# ProPrj_USB__2026-03-28.net
KiCad netlist of a schematic drawn in EasyEDA Pro
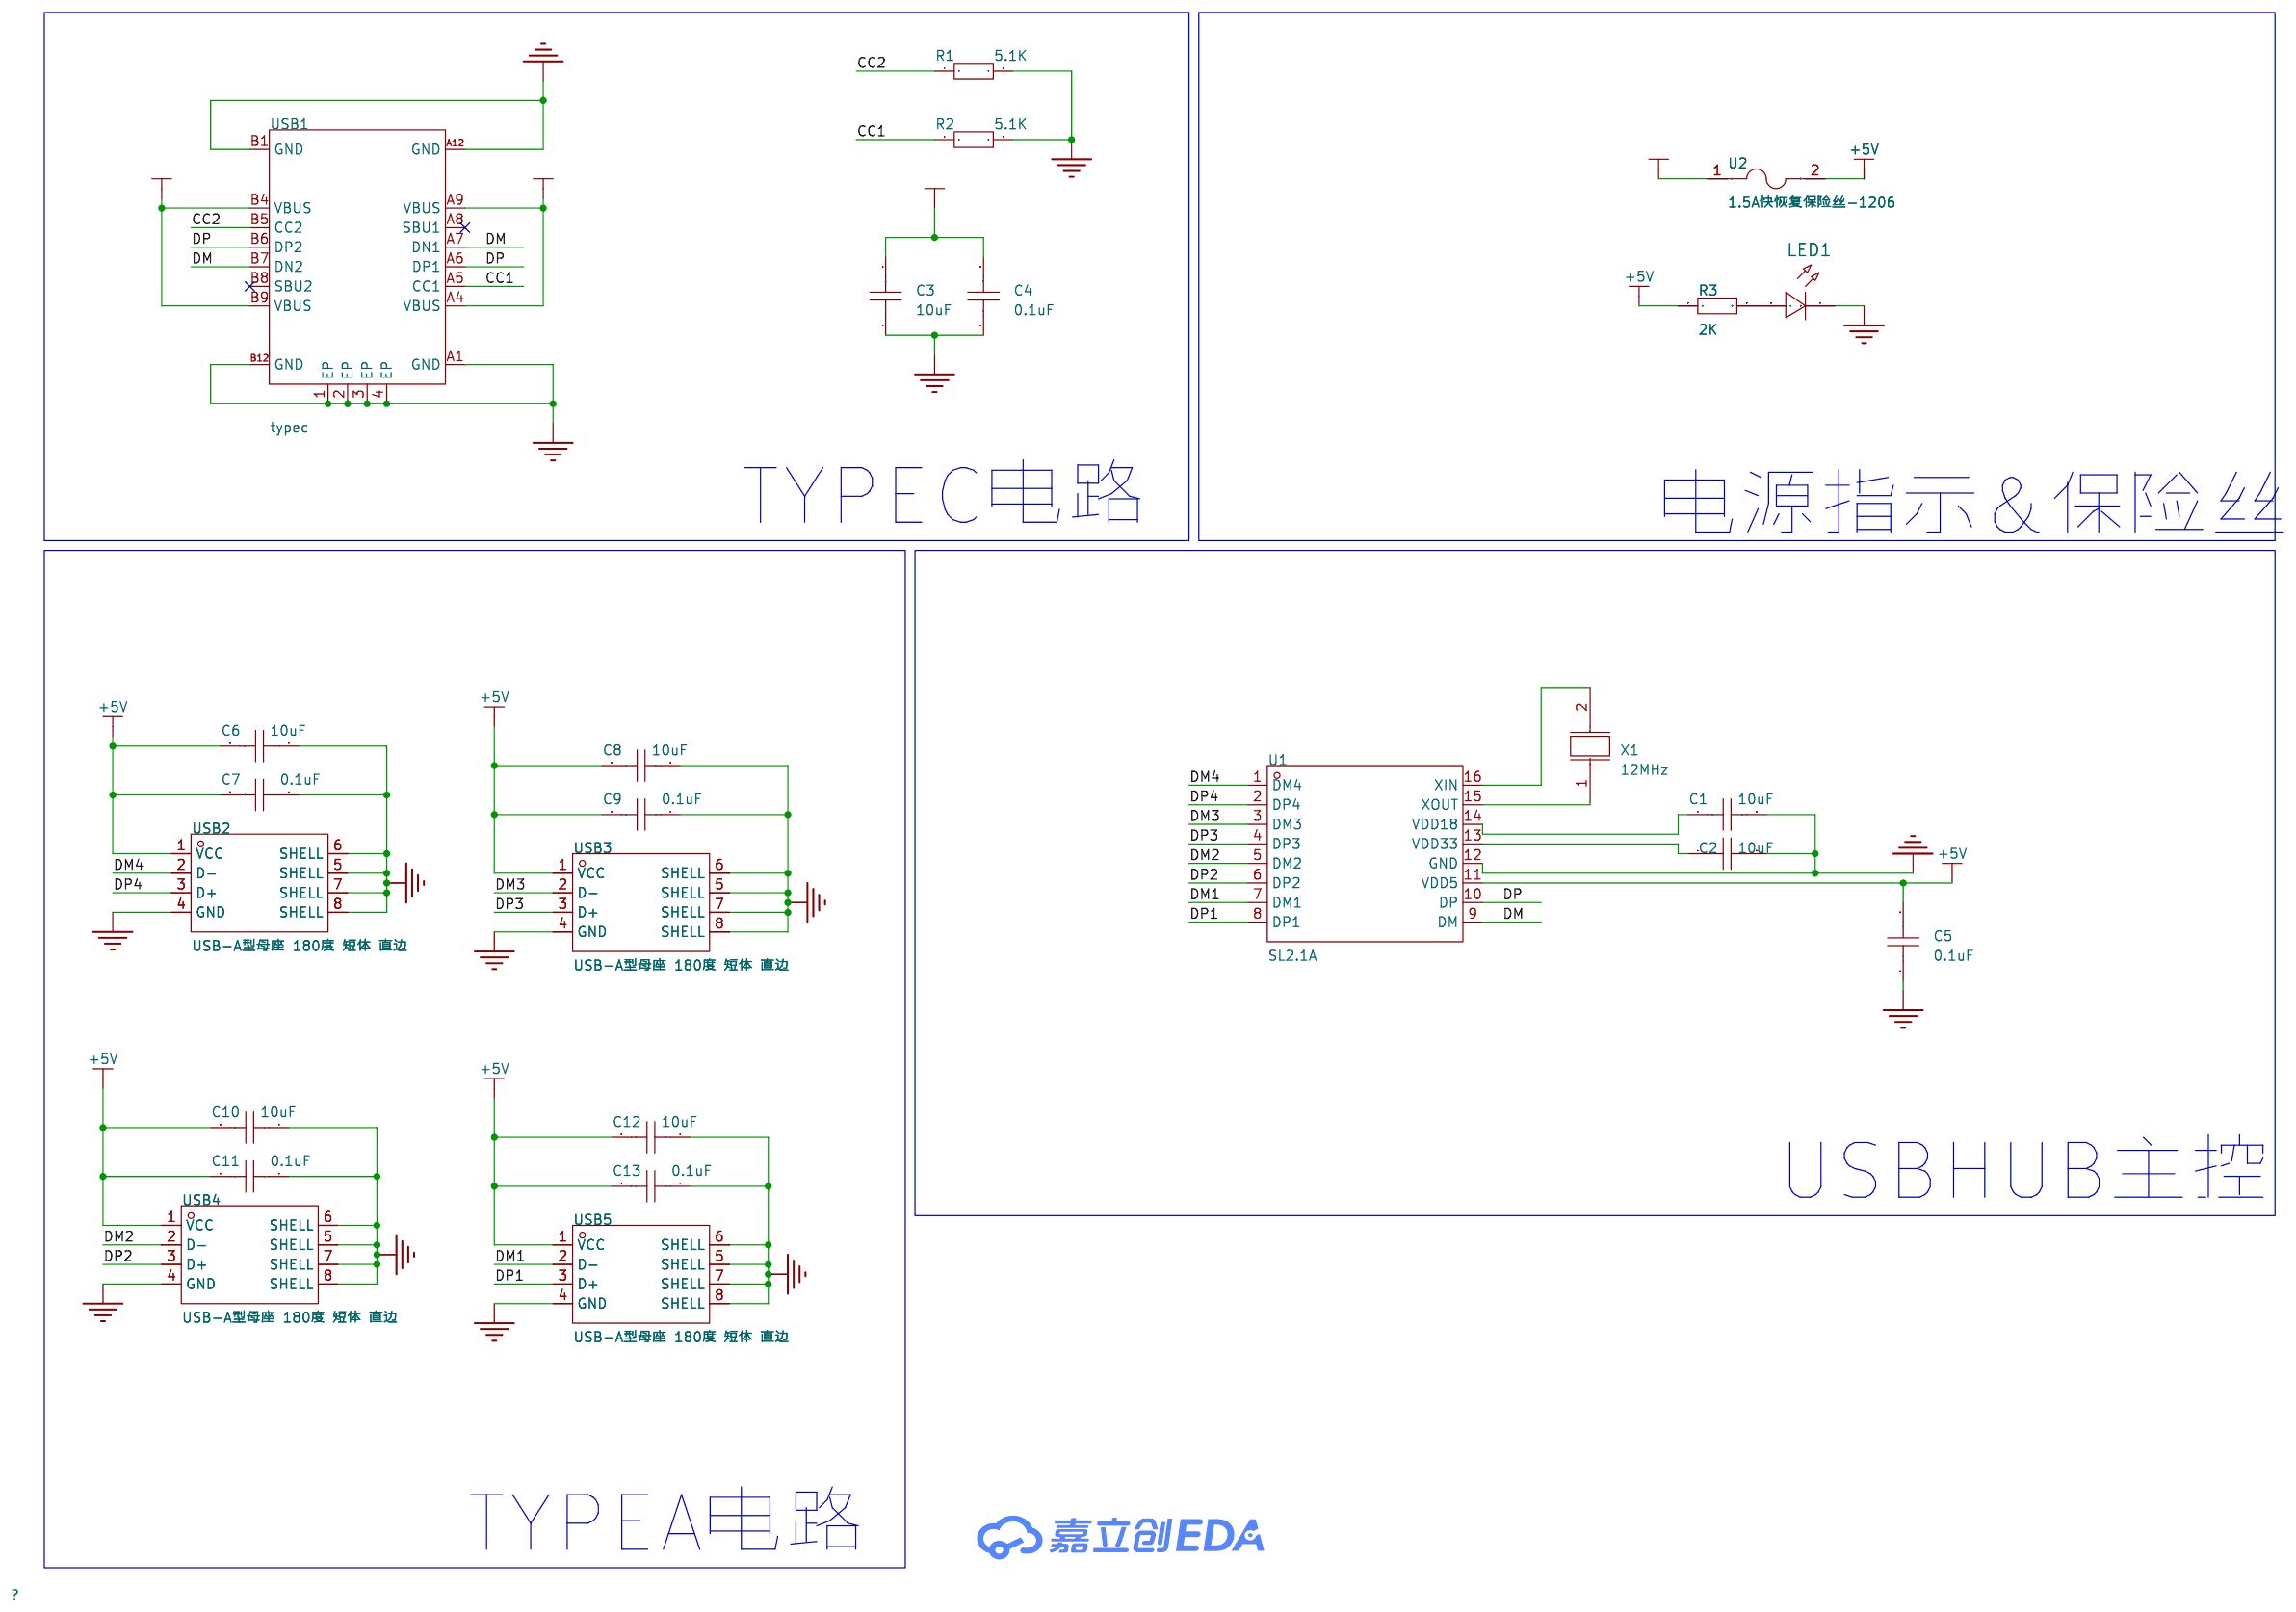
[diagram p0: schematic sheet]

(export (version "E")
  (design (tool "Eeschema 10.0.6"))
  (components
    (comp (ref "C1")
      (value "10uF")
      (footprint "easyedapro:C0805")
      (libsource (lib "easyedapro") (part "Capacitance"))
    )
    (comp (ref "C2")
      (value "10uF")
      (footprint "easyedapro:C0805")
      (libsource (lib "easyedapro") (part "Capacitance"))
    )
    (comp (ref "C3")
      (value "10uF")
      (footprint "easyedapro:C0805")
      (libsource (lib "easyedapro") (part "Capacitance"))
    )
    (comp (ref "C4")
      (value "0.1uF")
      (footprint "easyedapro:C0805")
      (libsource (lib "easyedapro") (part "Capacitance"))
    )
    (comp (ref "C5")
      (value "0.1uF")
      (footprint "easyedapro:C0805")
      (libsource (lib "easyedapro") (part "Capacitance"))
    )
    (comp (ref "C6")
      (value "10uF")
      (footprint "easyedapro:C0805")
      (libsource (lib "easyedapro") (part "Capacitance"))
    )
    (comp (ref "C7")
      (value "0.1uF")
      (footprint "easyedapro:C0805")
      (libsource (lib "easyedapro") (part "Capacitance"))
    )
    (comp (ref "C8")
      (value "10uF")
      (footprint "easyedapro:C0805")
      (libsource (lib "easyedapro") (part "Capacitance"))
    )
    (comp (ref "C9")
      (value "0.1uF")
      (footprint "easyedapro:C0805")
      (libsource (lib "easyedapro") (part "Capacitance"))
    )
    (comp (ref "C10")
      (value "10uF")
      (footprint "easyedapro:C0805")
      (libsource (lib "easyedapro") (part "Capacitance"))
    )
    (comp (ref "C11")
      (value "0.1uF")
      (footprint "easyedapro:C0805")
      (libsource (lib "easyedapro") (part "Capacitance"))
    )
    (comp (ref "C12")
      (value "10uF")
      (footprint "easyedapro:C0805")
      (libsource (lib "easyedapro") (part "Capacitance"))
    )
    (comp (ref "C13")
      (value "0.1uF")
      (footprint "easyedapro:C0805")
      (libsource (lib "easyedapro") (part "Capacitance"))
    )
    (comp (ref "LED1")
      (value "~")
      (footprint "easyedapro:LED_0805")
      (libsource (lib "easyedapro") (part "LED_R"))
    )
    (comp (ref "R1") (value "5.1K") (footprint "easyedapro:R0805") (libsource (lib "easyedapro") (part "电阻")))
    (comp (ref "R2") (value "5.1K") (footprint "easyedapro:R0805") (libsource (lib "easyedapro") (part "电阻")))
    (comp (ref "R3") (value "2K") (footprint "easyedapro:R0805") (libsource (lib "easyedapro") (part "电阻")))
    (comp (ref "U1")
      (value "SL2.1A")
      (footprint "easyedapro:SOP-16_L10.0-W3.9-P1.27-LS6.0-BL")
      (description "SL2.1A是一颗高集成度,高性能,低功耗的USB2.0集线器主控芯片，支持USB2.0高速(480MHz),全速(12MHz)和低速模式(1.5MHz)，内置12MHz晶体振荡器。")
      (fields (field (name "Manufacturer") "CoreChips(和芯润德)"))
      (libsource (lib "easyedapro") (part "SL2.1A"))
    )
    (comp (ref "U2")
      (value "1.5A快恢复保险丝-1206")
      (footprint "easyedapro:F1206")
      (libsource (lib "easyedapro") (part "1.5A快恢复保险丝-1206"))
    )
    (comp (ref "USB1")
      (value "typec")
      (footprint "easyedapro:USB-C-SMD_KH-TYPE-C-16P")
      (libsource (lib "easyedapro") (part "TYPEC_C9900016956"))
    )
    (comp (ref "USB2")
      (value "USB-A型母座 180度 短体 直边")
      (footprint "easyedapro:USB-A-SMD_WT_C9900004571")
      (libsource (lib "easyedapro") (part "USB-A型母座 180度 短体 直边"))
    )
    (comp (ref "USB3")
      (value "USB-A型母座 180度 短体 直边")
      (footprint "easyedapro:USB-A-SMD_WT_C9900004571")
      (libsource (lib "easyedapro") (part "USB-A型母座 180度 短体 直边"))
    )
    (comp (ref "USB4")
      (value "USB-A型母座 180度 短体 直边")
      (footprint "easyedapro:USB-A-SMD_WT_C9900004571")
      (libsource (lib "easyedapro") (part "USB-A型母座 180度 短体 直边"))
    )
    (comp (ref "USB5")
      (value "USB-A型母座 180度 短体 直边")
      (footprint "easyedapro:USB-A-SMD_WT_C9900004571")
      (libsource (lib "easyedapro") (part "USB-A型母座 180度 短体 直边"))
    )
    (comp (ref "X1")
      (value "12MHz")
      (footprint "easyedapro:CRYSTAL-SMD_L5.0-W3.2-1-A")
      (libsource (lib "easyedapro") (part "12MHZ"))
    )
  )
  (nets
    (net (code "1") (name "+5V") (class "Default")
      (node (ref "C10") (pin "2") (pinfunction "2_2") (pintype "input"))
      (node (ref "C11") (pin "2") (pinfunction "2_2") (pintype "input"))
      (node (ref "C12") (pin "2") (pinfunction "2_2") (pintype "input"))
      (node (ref "C13") (pin "2") (pinfunction "2_2") (pintype "input"))
      (node (ref "C5") (pin "2") (pinfunction "2_2") (pintype "input"))
      (node (ref "C6") (pin "2") (pinfunction "2_2") (pintype "input"))
      (node (ref "C7") (pin "2") (pinfunction "2_2") (pintype "input"))
      (node (ref "C8") (pin "2") (pinfunction "2_2") (pintype "input"))
      (node (ref "C9") (pin "2") (pinfunction "2_2") (pintype "input"))
      (node (ref "R3") (pin "1") (pinfunction "1_1") (pintype "input"))
      (node (ref "U1") (pin "11") (pinfunction "VDD5_11") (pintype "unspecified"))
      (node (ref "U2") (pin "2") (pinfunction "2_2") (pintype "unspecified"))
      (node (ref "USB2") (pin "1") (pinfunction "VCC_1") (pintype "unspecified"))
      (node (ref "USB3") (pin "1") (pinfunction "VCC_1") (pintype "unspecified"))
      (node (ref "USB4") (pin "1") (pinfunction "VCC_1") (pintype "unspecified"))
      (node (ref "USB5") (pin "1") (pinfunction "VCC_1") (pintype "unspecified"))
    )
    (net (code "2") (name "/CC1") (class "Default")
      (node (ref "R2") (pin "1") (pinfunction "1_1") (pintype "input"))
      (node (ref "USB1") (pin "A5") (pinfunction "CC1_A5") (pintype "unspecified"))
    )
    (net (code "3") (name "/CC2") (class "Default")
      (node (ref "R1") (pin "1") (pinfunction "1_1") (pintype "input"))
      (node (ref "USB1") (pin "B5") (pinfunction "CC2_B5") (pintype "unspecified"))
    )
    (net (code "4") (name "/DM") (class "Default")
      (node (ref "U1") (pin "9") (pinfunction "DM_9") (pintype "unspecified"))
      (node (ref "USB1") (pin "A7") (pinfunction "DN1_A7") (pintype "unspecified"))
      (node (ref "USB1") (pin "B7") (pinfunction "DN2_B7") (pintype "unspecified"))
    )
    (net (code "5") (name "/DM1") (class "Default")
      (node (ref "U1") (pin "7") (pinfunction "DM1_7") (pintype "unspecified"))
      (node (ref "USB5") (pin "2") (pinfunction "D-_2") (pintype "unspecified"))
    )
    (net (code "6") (name "/DM2") (class "Default")
      (node (ref "U1") (pin "5") (pinfunction "DM2_5") (pintype "unspecified"))
      (node (ref "USB4") (pin "2") (pinfunction "D-_2") (pintype "unspecified"))
    )
    (net (code "7") (name "/DM3") (class "Default")
      (node (ref "U1") (pin "3") (pinfunction "DM3_3") (pintype "unspecified"))
      (node (ref "USB3") (pin "2") (pinfunction "D-_2") (pintype "unspecified"))
    )
    (net (code "8") (name "/DM4") (class "Default")
      (node (ref "U1") (pin "1") (pinfunction "DM4_1") (pintype "unspecified"))
      (node (ref "USB2") (pin "2") (pinfunction "D-_2") (pintype "unspecified"))
    )
    (net (code "9") (name "/DP") (class "Default")
      (node (ref "U1") (pin "10") (pinfunction "DP_10") (pintype "unspecified"))
      (node (ref "USB1") (pin "A6") (pinfunction "DP1_A6") (pintype "unspecified"))
      (node (ref "USB1") (pin "B6") (pinfunction "DP2_B6") (pintype "unspecified"))
    )
    (net (code "10") (name "/DP1") (class "Default")
      (node (ref "U1") (pin "8") (pinfunction "DP1_8") (pintype "unspecified"))
      (node (ref "USB5") (pin "3") (pinfunction "D+_3") (pintype "unspecified"))
    )
    (net (code "11") (name "/DP2") (class "Default")
      (node (ref "U1") (pin "6") (pinfunction "DP2_6") (pintype "unspecified"))
      (node (ref "USB4") (pin "3") (pinfunction "D+_3") (pintype "unspecified"))
    )
    (net (code "12") (name "/DP3") (class "Default")
      (node (ref "U1") (pin "4") (pinfunction "DP3_4") (pintype "unspecified"))
      (node (ref "USB3") (pin "3") (pinfunction "D+_3") (pintype "unspecified"))
    )
    (net (code "13") (name "/DP4") (class "Default")
      (node (ref "U1") (pin "2") (pinfunction "DP4_2") (pintype "unspecified"))
      (node (ref "USB2") (pin "3") (pinfunction "D+_3") (pintype "unspecified"))
    )
    (net (code "14") (name "GND") (class "Default")
      (node (ref "C1") (pin "2") (pinfunction "2_2") (pintype "input"))
      (node (ref "C10") (pin "1") (pinfunction "1_1") (pintype "input"))
      (node (ref "C11") (pin "1") (pinfunction "1_1") (pintype "input"))
      (node (ref "C12") (pin "1") (pinfunction "1_1") (pintype "input"))
      (node (ref "C13") (pin "1") (pinfunction "1_1") (pintype "input"))
      (node (ref "C2") (pin "2") (pinfunction "2_2") (pintype "input"))
      (node (ref "C3") (pin "1") (pinfunction "1_1") (pintype "input"))
      (node (ref "C4") (pin "1") (pinfunction "1_1") (pintype "input"))
      (node (ref "C5") (pin "1") (pinfunction "1_1") (pintype "input"))
      (node (ref "C6") (pin "1") (pinfunction "1_1") (pintype "input"))
      (node (ref "C7") (pin "1") (pinfunction "1_1") (pintype "input"))
      (node (ref "C8") (pin "1") (pinfunction "1_1") (pintype "input"))
      (node (ref "C9") (pin "1") (pinfunction "1_1") (pintype "input"))
      (node (ref "LED1") (pin "1") (pinfunction "C_1") (pintype "input"))
      (node (ref "R1") (pin "2") (pinfunction "2_2") (pintype "input"))
      (node (ref "R2") (pin "2") (pinfunction "2_2") (pintype "input"))
      (node (ref "U1") (pin "12") (pinfunction "GND_12") (pintype "unspecified"))
      (node (ref "USB1") (pin "1") (pinfunction "EP_1") (pintype "unspecified"))
      (node (ref "USB1") (pin "2") (pinfunction "EP_2") (pintype "unspecified"))
      (node (ref "USB1") (pin "3") (pinfunction "EP_3") (pintype "unspecified"))
      (node (ref "USB1") (pin "4") (pinfunction "EP_4") (pintype "unspecified"))
      (node (ref "USB1") (pin "A1") (pinfunction "GND_A1") (pintype "unspecified"))
      (node (ref "USB1") (pin "A12") (pinfunction "GND_A12") (pintype "unspecified"))
      (node (ref "USB1") (pin "B1") (pinfunction "GND_B1") (pintype "unspecified"))
      (node (ref "USB1") (pin "B12") (pinfunction "GND_B12") (pintype "unspecified"))
      (node (ref "USB2") (pin "4") (pinfunction "GND_4") (pintype "unspecified"))
      (node (ref "USB2") (pin "5") (pinfunction "SHELL_5") (pintype "unspecified"))
      (node (ref "USB2") (pin "6") (pinfunction "SHELL_6") (pintype "unspecified"))
      (node (ref "USB2") (pin "7") (pinfunction "SHELL_7") (pintype "unspecified"))
      (node (ref "USB2") (pin "8") (pinfunction "SHELL_8") (pintype "unspecified"))
      (node (ref "USB3") (pin "4") (pinfunction "GND_4") (pintype "unspecified"))
      (node (ref "USB3") (pin "5") (pinfunction "SHELL_5") (pintype "unspecified"))
      (node (ref "USB3") (pin "6") (pinfunction "SHELL_6") (pintype "unspecified"))
      (node (ref "USB3") (pin "7") (pinfunction "SHELL_7") (pintype "unspecified"))
      (node (ref "USB3") (pin "8") (pinfunction "SHELL_8") (pintype "unspecified"))
      (node (ref "USB4") (pin "4") (pinfunction "GND_4") (pintype "unspecified"))
      (node (ref "USB4") (pin "5") (pinfunction "SHELL_5") (pintype "unspecified"))
      (node (ref "USB4") (pin "6") (pinfunction "SHELL_6") (pintype "unspecified"))
      (node (ref "USB4") (pin "7") (pinfunction "SHELL_7") (pintype "unspecified"))
      (node (ref "USB4") (pin "8") (pinfunction "SHELL_8") (pintype "unspecified"))
      (node (ref "USB5") (pin "4") (pinfunction "GND_4") (pintype "unspecified"))
      (node (ref "USB5") (pin "5") (pinfunction "SHELL_5") (pintype "unspecified"))
      (node (ref "USB5") (pin "6") (pinfunction "SHELL_6") (pintype "unspecified"))
      (node (ref "USB5") (pin "7") (pinfunction "SHELL_7") (pintype "unspecified"))
      (node (ref "USB5") (pin "8") (pinfunction "SHELL_8") (pintype "unspecified"))
    )
    (net (code "15") (name "Net-(LED1-A)") (class "Default")
      (node (ref "LED1") (pin "2") (pinfunction "A_2") (pintype "input"))
      (node (ref "R3") (pin "2") (pinfunction "2_2") (pintype "input"))
    )
    (net (code "16") (name "Net-(U1-VDD18)") (class "Default")
      (node (ref "C1") (pin "1") (pinfunction "1_1") (pintype "input"))
      (node (ref "U1") (pin "14") (pinfunction "VDD18_14") (pintype "unspecified"))
    )
    (net (code "17") (name "Net-(U1-VDD33)") (class "Default")
      (node (ref "C2") (pin "1") (pinfunction "1_1") (pintype "input"))
      (node (ref "U1") (pin "13") (pinfunction "VDD33_13") (pintype "unspecified"))
    )
    (net (code "18") (name "Net-(U1-XIN)") (class "Default")
      (node (ref "U1") (pin "16") (pinfunction "XIN_16") (pintype "unspecified"))
      (node (ref "X1") (pin "2") (pinfunction "2_2") (pintype "unspecified"))
    )
    (net (code "19") (name "Net-(U1-XOUT)") (class "Default")
      (node (ref "U1") (pin "15") (pinfunction "XOUT_15") (pintype "unspecified"))
      (node (ref "X1") (pin "1") (pinfunction "1_1") (pintype "unspecified"))
    )
    (net (code "20") (name "VCC+5V") (class "Default")
      (node (ref "C3") (pin "2") (pinfunction "2_2") (pintype "input"))
      (node (ref "C4") (pin "2") (pinfunction "2_2") (pintype "input"))
      (node (ref "U2") (pin "1") (pinfunction "1_1") (pintype "unspecified"))
      (node (ref "USB1") (pin "A4") (pinfunction "VBUS_A4") (pintype "unspecified"))
      (node (ref "USB1") (pin "A9") (pinfunction "VBUS_A9") (pintype "unspecified"))
      (node (ref "USB1") (pin "B4") (pinfunction "VBUS_B4") (pintype "unspecified"))
      (node (ref "USB1") (pin "B9") (pinfunction "VBUS_B9") (pintype "unspecified"))
    )
    (net (code "21") (name "unconnected-(USB1-SBU1-PadA8)") (class "Default")
      (node (ref "USB1") (pin "A8") (pinfunction "SBU1_A8") (pintype "unspecified+no_connect"))
    )
    (net (code "22") (name "unconnected-(USB1-SBU2-PadB8)") (class "Default")
      (node (ref "USB1") (pin "B8") (pinfunction "SBU2_B8") (pintype "unspecified+no_connect"))
    )
  )
)
